# uino-1284p.net
KiCad netlist of a schematic drawn in EAGLE
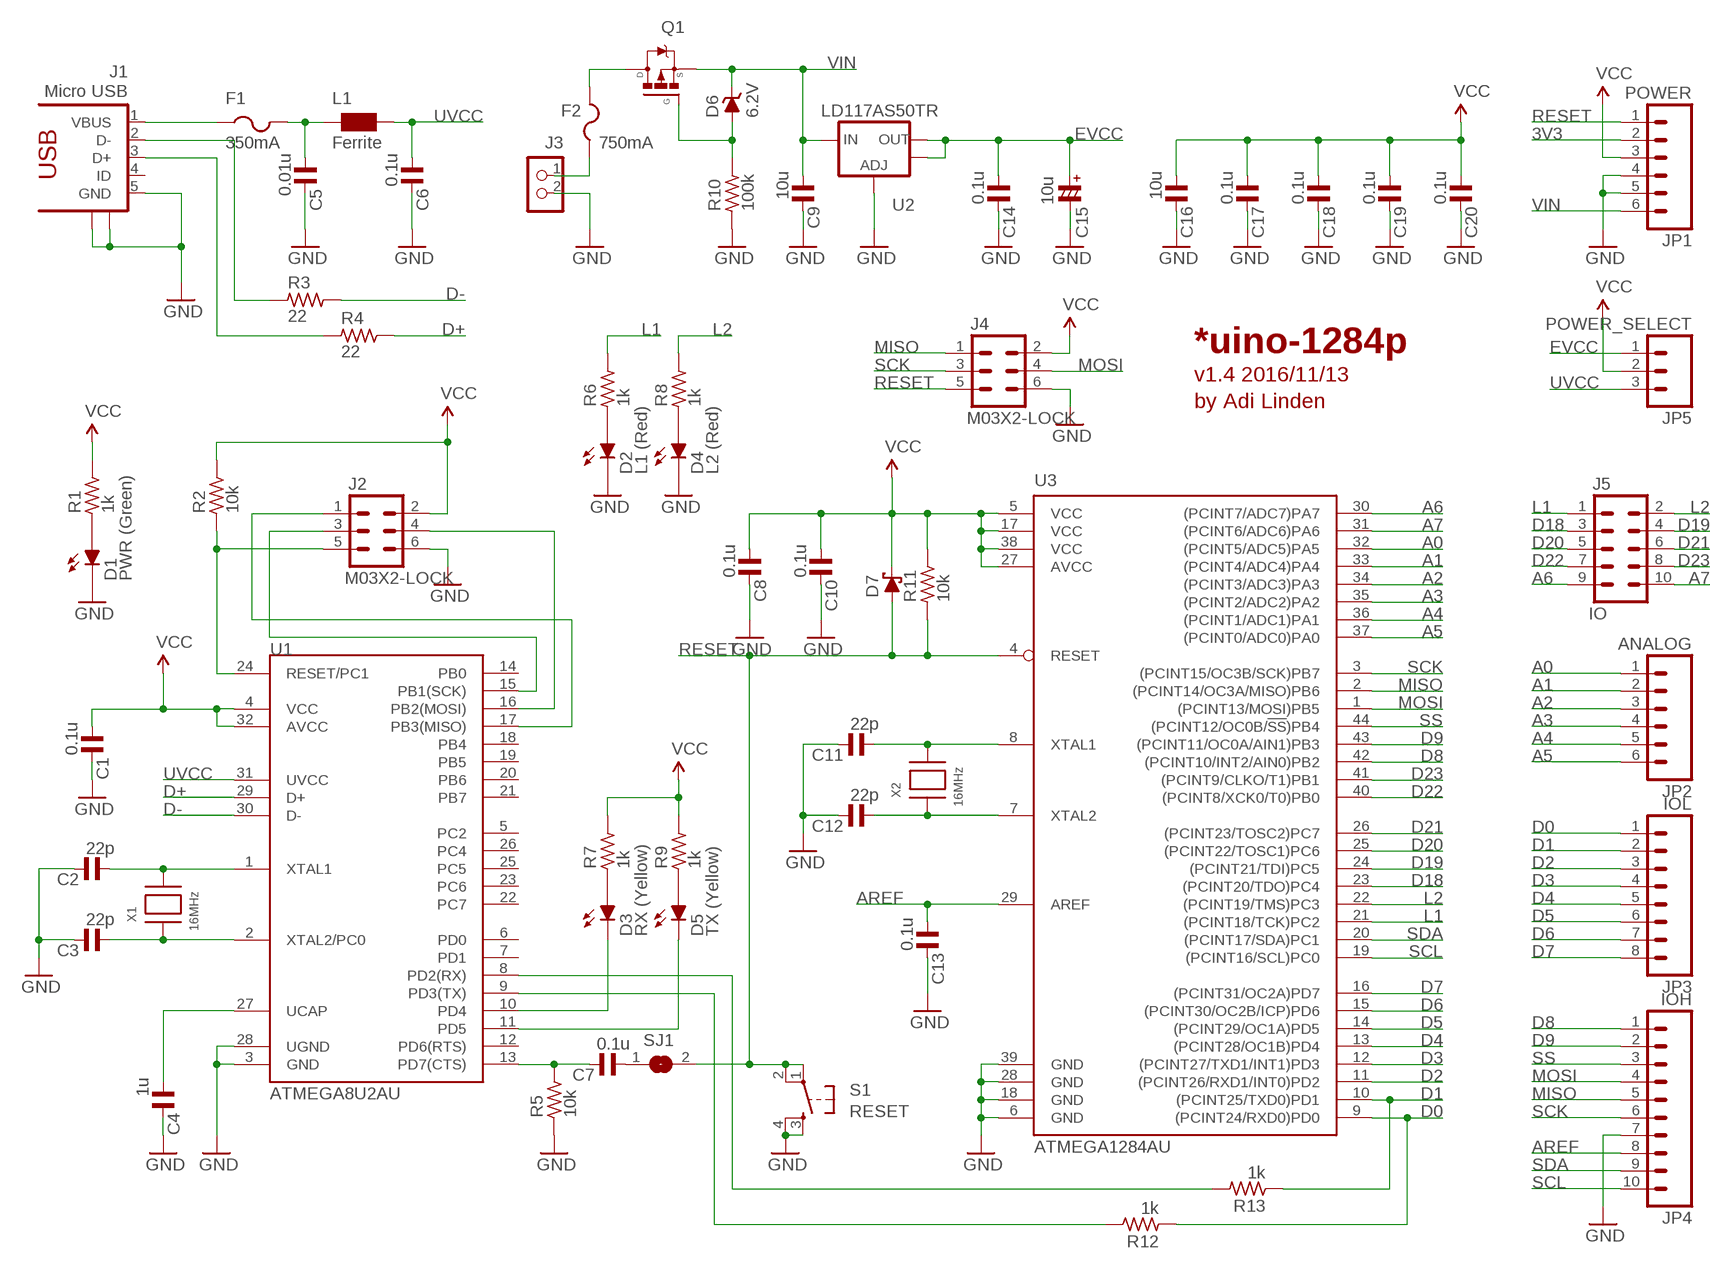
[diagram p0: schematic, sheet 1]

(export (version "E")
  (design (tool "Eeschema 10.0.6"))
  (components
    (comp (ref "C1")
      (value "0.1u")
      (footprint "eagle-import:C0805MP")
      (libsource (lib "eagle-import") (part "C_0805MP"))
    )
    (comp (ref "C2")
      (value "22p")
      (footprint "eagle-import:C0805MP")
      (libsource (lib "eagle-import") (part "C_0805MP"))
    )
    (comp (ref "C3")
      (value "22p")
      (footprint "eagle-import:C0805MP")
      (libsource (lib "eagle-import") (part "C_0805MP"))
    )
    (comp (ref "C4")
      (value "1u")
      (footprint "eagle-import:C0805MP")
      (libsource (lib "eagle-import") (part "C_0805MP"))
    )
    (comp (ref "C5")
      (value "0.01u")
      (footprint "eagle-import:C0805MP")
      (libsource (lib "eagle-import") (part "C_0805MP"))
    )
    (comp (ref "C6")
      (value "0.1u")
      (footprint "eagle-import:C0805MP")
      (libsource (lib "eagle-import") (part "C_0805MP"))
    )
    (comp (ref "C7")
      (value "0.1u")
      (footprint "eagle-import:C0805MP")
      (libsource (lib "eagle-import") (part "C_0805MP"))
    )
    (comp (ref "C8")
      (value "0.1u")
      (footprint "eagle-import:C0805MP")
      (libsource (lib "eagle-import") (part "C_0805MP"))
    )
    (comp (ref "C9")
      (value "10u")
      (footprint "eagle-import:C0805MP")
      (libsource (lib "eagle-import") (part "C_0805MP"))
    )
    (comp (ref "C10")
      (value "0.1u")
      (footprint "eagle-import:C0805MP")
      (libsource (lib "eagle-import") (part "C_0805MP"))
    )
    (comp (ref "C11")
      (value "22p")
      (footprint "eagle-import:C0805MP")
      (libsource (lib "eagle-import") (part "C_0805MP"))
    )
    (comp (ref "C12")
      (value "22p")
      (footprint "eagle-import:C0805MP")
      (libsource (lib "eagle-import") (part "C_0805MP"))
    )
    (comp (ref "C13")
      (value "0.1u")
      (footprint "eagle-import:C0805MP")
      (libsource (lib "eagle-import") (part "C_0805MP"))
    )
    (comp (ref "C14")
      (value "0.1u")
      (footprint "eagle-import:C0805MP")
      (libsource (lib "eagle-import") (part "C_0805MP"))
    )
    (comp (ref "C15")
      (value "10u")
      (footprint "eagle-import:C0805MP_T")
      (libsource (lib "eagle-import") (part "CP_0805MP/T"))
    )
    (comp (ref "C16")
      (value "10u")
      (footprint "eagle-import:C0805MP")
      (libsource (lib "eagle-import") (part "C_0805MP"))
    )
    (comp (ref "C17")
      (value "0.1u")
      (footprint "eagle-import:C0805MP")
      (libsource (lib "eagle-import") (part "C_0805MP"))
    )
    (comp (ref "C18")
      (value "0.1u")
      (footprint "eagle-import:C0805MP")
      (libsource (lib "eagle-import") (part "C_0805MP"))
    )
    (comp (ref "C19")
      (value "0.1u")
      (footprint "eagle-import:C0805MP")
      (libsource (lib "eagle-import") (part "C_0805MP"))
    )
    (comp (ref "C20")
      (value "0.1u")
      (footprint "eagle-import:C0805MP")
      (libsource (lib "eagle-import") (part "C_0805MP"))
    )
    (comp (ref "D1")
      (value "PWR (Green)")
      (footprint "eagle-import:CHIP-LED0805MP")
      (libsource (lib "eagle-import") (part "LEDCHIP-LED0805MP"))
    )
    (comp (ref "D2")
      (value "L1 (Red)")
      (footprint "eagle-import:CHIP-LED0805MP")
      (libsource (lib "eagle-import") (part "LEDCHIP-LED0805MP"))
    )
    (comp (ref "D3")
      (value "RX (Yellow)")
      (footprint "eagle-import:CHIP-LED0805MP")
      (libsource (lib "eagle-import") (part "LEDCHIP-LED0805MP"))
    )
    (comp (ref "D4")
      (value "L2 (Red)")
      (footprint "eagle-import:CHIP-LED0805MP")
      (libsource (lib "eagle-import") (part "LEDCHIP-LED0805MP"))
    )
    (comp (ref "D5")
      (value "TX (Yellow)")
      (footprint "eagle-import:CHIP-LED0805MP")
      (libsource (lib "eagle-import") (part "LEDCHIP-LED0805MP"))
    )
    (comp (ref "D6")
      (value "6.2V")
      (footprint "eagle-import:SOD323")
      (libsource (lib "eagle-import") (part "BZX384"))
    )
    (comp (ref "D7")
      (value "SCHOTTKY-DIODESOD323")
      (footprint "eagle-import:SOD323")
      (libsource (lib "eagle-import") (part "SCHOTTKY-DIODESOD323"))
    )
    (comp (ref "F1")
      (value "350mA")
      (footprint "eagle-import:R0805")
      (libsource (lib "eagle-import") (part "PTCFUSE-0805"))
    )
    (comp (ref "F2")
      (value "750mA")
      (footprint "eagle-import:R0805")
      (libsource (lib "eagle-import") (part "PTCFUSE-0805"))
    )
    (comp (ref "J1")
      (value "Micro USB")
      (footprint "eagle-import:ZX62D-AB-5P8")
      (libsource (lib "eagle-import") (part "USB_MICRO_B_2.0-TH"))
    )
    (comp (ref "J2")
      (value "M03X2-LOCK")
      (footprint "eagle-import:2X03_LOCK")
      (libsource (lib "eagle-import") (part "M03X2-LOCK"))
    )
    (comp (ref "J3")
      (value "CON_TERMINAL_BLOCK_02-5MM")
      (footprint "eagle-import:TERMINAL_BLOCK_2P_5")
      (libsource (lib "eagle-import") (part "CON_TERMINAL_BLOCK_02-5MM"))
    )
    (comp (ref "J4")
      (value "M03X2-LOCK")
      (footprint "eagle-import:2X03_LOCK")
      (libsource (lib "eagle-import") (part "M03X2-LOCK"))
    )
    (comp (ref "J5")
      (value "IO")
      (footprint "eagle-import:2X05")
      (libsource (lib "eagle-import") (part "M05X2"))
    )
    (comp (ref "JP1")
      (value "POWER")
      (footprint "eagle-import:1X06")
      (libsource (lib "eagle-import") (part "M06SIP"))
    )
    (comp (ref "JP2")
      (value "ANALOG")
      (footprint "eagle-import:1X06")
      (libsource (lib "eagle-import") (part "M06SIP"))
    )
    (comp (ref "JP3")
      (value "IOL")
      (footprint "eagle-import:1X08")
      (libsource (lib "eagle-import") (part "M081X08"))
    )
    (comp (ref "JP4")
      (value "IOH")
      (footprint "eagle-import:1X10")
      (libsource (lib "eagle-import") (part "M101X10"))
    )
    (comp (ref "JP5")
      (value "POWER_SELECT")
      (footprint "eagle-import:1X03")
      (libsource (lib "eagle-import") (part "M03PTH"))
    )
    (comp (ref "L1")
      (value "Ferrite")
      (footprint "eagle-import:0805")
      (libsource (lib "eagle-import") (part "WE-CBF_0805"))
    )
    (comp (ref "Q1")
      (value "MMBF0202PLT1")
      (footprint "eagle-import:SOT23")
      (libsource (lib "eagle-import") (part "MMBF0202PLT1"))
    )
    (comp (ref "R1")
      (value "1k")
      (footprint "eagle-import:R0805MP")
      (libsource (lib "eagle-import") (part "R_0805MP"))
    )
    (comp (ref "R2")
      (value "10k")
      (footprint "eagle-import:R0805MP")
      (libsource (lib "eagle-import") (part "R_0805MP"))
    )
    (comp (ref "R3")
      (value "22")
      (footprint "eagle-import:R0805MP")
      (libsource (lib "eagle-import") (part "R_0805MP"))
    )
    (comp (ref "R4")
      (value "22")
      (footprint "eagle-import:R0805MP")
      (libsource (lib "eagle-import") (part "R_0805MP"))
    )
    (comp (ref "R5")
      (value "10k")
      (footprint "eagle-import:R0805MP")
      (libsource (lib "eagle-import") (part "R_0805MP"))
    )
    (comp (ref "R6")
      (value "1k")
      (footprint "eagle-import:R0805MP")
      (libsource (lib "eagle-import") (part "R_0805MP"))
    )
    (comp (ref "R7")
      (value "1k")
      (footprint "eagle-import:R0805MP")
      (libsource (lib "eagle-import") (part "R_0805MP"))
    )
    (comp (ref "R8")
      (value "1k")
      (footprint "eagle-import:R0805MP")
      (libsource (lib "eagle-import") (part "R_0805MP"))
    )
    (comp (ref "R9")
      (value "1k")
      (footprint "eagle-import:R0805MP")
      (libsource (lib "eagle-import") (part "R_0805MP"))
    )
    (comp (ref "R10")
      (value "100k")
      (footprint "eagle-import:R0805MP")
      (libsource (lib "eagle-import") (part "R_0805MP"))
    )
    (comp (ref "R11")
      (value "10k")
      (footprint "eagle-import:R0805MP")
      (libsource (lib "eagle-import") (part "R_0805MP"))
    )
    (comp (ref "R12")
      (value "1k")
      (footprint "eagle-import:R0805MP")
      (libsource (lib "eagle-import") (part "R_0805MP"))
    )
    (comp (ref "R13")
      (value "1k")
      (footprint "eagle-import:R0805MP")
      (libsource (lib "eagle-import") (part "R_0805MP"))
    )
    (comp (ref "S1")
      (value "RESET")
      (footprint "eagle-import:TACTILE_SWITCH_SMD")
      (libsource (lib "eagle-import") (part "TAC_SWITCHSMD"))
    )
    (comp (ref "SJ1") (value "SJ") (footprint "eagle-import:SJ") (libsource (lib "eagle-import") (part "SJ")))
    (comp (ref "U1")
      (value "ATMEGA8U2AU")
      (footprint "eagle-import:TQFP32-08")
      (libsource (lib "eagle-import") (part "ATMEGA8U2AU"))
    )
    (comp (ref "U2")
      (value "LD117AS50TR")
      (footprint "eagle-import:SOT223")
      (libsource (lib "eagle-import") (part "V_REG_LM1117SOT223"))
    )
    (comp (ref "U3")
      (value "ATMEGA1284AU")
      (footprint "eagle-import:TQFP44")
      (fields (field (name "MPN") "ATMEGA644PV-10AU"))
      (libsource (lib "eagle-import") (part "ATMEGA1284P-AU"))
    )
    (comp (ref "X1")
      (value "16MHz")
      (footprint "eagle-import:NX5032")
      (libsource (lib "eagle-import") (part "XTALNX5032"))
    )
    (comp (ref "X2")
      (value "16MHz")
      (footprint "eagle-import:NX5032")
      (libsource (lib "eagle-import") (part "XTALNX5032"))
    )
  )
  (nets
    (net (code "1") (name "/3V3") (class "Default")
      (node (ref "JP1") (pin "2") (pinfunction "2_2") (pintype "passive"))
    )
    (net (code "2") (name "/A0") (class "Default")
      (node (ref "JP2") (pin "1") (pinfunction "1_1") (pintype "passive"))
      (node (ref "U3") (pin "32") (pinfunction "(PCINT5/ADC5)PA5_32") (pintype "bidirectional"))
    )
    (net (code "3") (name "/A1") (class "Default")
      (node (ref "JP2") (pin "2") (pinfunction "2_2") (pintype "passive"))
      (node (ref "U3") (pin "33") (pinfunction "(PCINT4/ADC4)PA4_33") (pintype "bidirectional"))
    )
    (net (code "4") (name "/A2") (class "Default")
      (node (ref "JP2") (pin "3") (pinfunction "3_3") (pintype "passive"))
      (node (ref "U3") (pin "34") (pinfunction "(PCINT3/ADC3)PA3_34") (pintype "bidirectional"))
    )
    (net (code "5") (name "/A3") (class "Default")
      (node (ref "JP2") (pin "4") (pinfunction "4_4") (pintype "passive"))
      (node (ref "U3") (pin "35") (pinfunction "(PCINT2/ADC2)PA2_35") (pintype "bidirectional"))
    )
    (net (code "6") (name "/A4") (class "Default")
      (node (ref "JP2") (pin "5") (pinfunction "5_5") (pintype "passive"))
      (node (ref "U3") (pin "36") (pinfunction "(PCINT1/ADC1)PA1_36") (pintype "bidirectional"))
    )
    (net (code "7") (name "/A5") (class "Default")
      (node (ref "JP2") (pin "6") (pinfunction "6_6") (pintype "passive"))
      (node (ref "U3") (pin "37") (pinfunction "(PCINT0/ADC0)PA0_37") (pintype "bidirectional"))
    )
    (net (code "8") (name "/A6") (class "Default")
      (node (ref "J5") (pin "9") (pinfunction "9_9") (pintype "passive"))
      (node (ref "U3") (pin "30") (pinfunction "(PCINT7/ADC7)PA7_30") (pintype "bidirectional"))
    )
    (net (code "9") (name "/A7") (class "Default")
      (node (ref "J5") (pin "10") (pinfunction "10_10") (pintype "passive"))
      (node (ref "U3") (pin "31") (pinfunction "(PCINT6/ADC6)PA6_31") (pintype "bidirectional"))
    )
    (net (code "10") (name "/AREF") (class "Default")
      (node (ref "C13") (pin "1") (pinfunction "1_1") (pintype "passive"))
      (node (ref "JP4") (pin "8") (pinfunction "8_8") (pintype "passive"))
      (node (ref "U3") (pin "29") (pinfunction "AREF_29") (pintype "passive"))
    )
    (net (code "11") (name "/D+") (class "Default")
      (node (ref "R4") (pin "2") (pinfunction "2_2") (pintype "passive"))
      (node (ref "U1") (pin "29") (pinfunction "D+_29") (pintype "bidirectional"))
    )
    (net (code "12") (name "/D-") (class "Default")
      (node (ref "R3") (pin "2") (pinfunction "2_2") (pintype "passive"))
      (node (ref "U1") (pin "30") (pinfunction "D-_30") (pintype "bidirectional"))
    )
    (net (code "13") (name "/D0") (class "Default")
      (node (ref "JP3") (pin "1") (pinfunction "1_1") (pintype "passive"))
      (node (ref "R12") (pin "1") (pinfunction "1_1") (pintype "passive"))
      (node (ref "U3") (pin "9") (pinfunction "(PCINT24/RXD0)PD0_9") (pintype "bidirectional"))
    )
    (net (code "14") (name "/D1") (class "Default")
      (node (ref "JP3") (pin "2") (pinfunction "2_2") (pintype "passive"))
      (node (ref "R13") (pin "1") (pinfunction "1_1") (pintype "passive"))
      (node (ref "U3") (pin "10") (pinfunction "(PCINT25/TXD0)PD1_10") (pintype "bidirectional"))
    )
    (net (code "15") (name "/D2") (class "Default")
      (node (ref "JP3") (pin "3") (pinfunction "3_3") (pintype "passive"))
      (node (ref "U3") (pin "11") (pinfunction "(PCINT26/RXD1/INT0)PD2_11") (pintype "bidirectional"))
    )
    (net (code "16") (name "/D3") (class "Default")
      (node (ref "JP3") (pin "4") (pinfunction "4_4") (pintype "passive"))
      (node (ref "U3") (pin "12") (pinfunction "(PCINT27/TXD1/INT1)PD3_12") (pintype "bidirectional"))
    )
    (net (code "17") (name "/D4") (class "Default")
      (node (ref "JP3") (pin "5") (pinfunction "5_5") (pintype "passive"))
      (node (ref "U3") (pin "13") (pinfunction "(PCINT28/OC1B)PD4_13") (pintype "bidirectional"))
    )
    (net (code "18") (name "/D5") (class "Default")
      (node (ref "JP3") (pin "6") (pinfunction "6_6") (pintype "passive"))
      (node (ref "U3") (pin "14") (pinfunction "(PCINT29/OC1A)PD5_14") (pintype "bidirectional"))
    )
    (net (code "19") (name "/D6") (class "Default")
      (node (ref "JP3") (pin "7") (pinfunction "7_7") (pintype "passive"))
      (node (ref "U3") (pin "15") (pinfunction "(PCINT30/OC2B/ICP)PD6_15") (pintype "bidirectional"))
    )
    (net (code "20") (name "/D7") (class "Default")
      (node (ref "JP3") (pin "8") (pinfunction "8_8") (pintype "passive"))
      (node (ref "U3") (pin "16") (pinfunction "(PCINT31/OC2A)PD7_16") (pintype "bidirectional"))
    )
    (net (code "21") (name "/D8") (class "Default")
      (node (ref "JP4") (pin "1") (pinfunction "1_1") (pintype "passive"))
      (node (ref "U3") (pin "42") (pinfunction "(PCINT10/INT2/AIN0)PB2_42") (pintype "bidirectional"))
    )
    (net (code "22") (name "/D9") (class "Default")
      (node (ref "JP4") (pin "2") (pinfunction "2_2") (pintype "passive"))
      (node (ref "U3") (pin "43") (pinfunction "(PCINT11/OC0A/AIN1)PB3_43") (pintype "bidirectional"))
    )
    (net (code "23") (name "/D18") (class "Default")
      (node (ref "J5") (pin "3") (pinfunction "3_3") (pintype "passive"))
      (node (ref "U3") (pin "23") (pinfunction "(PCINT20/TDO)PC4_23") (pintype "output"))
    )
    (net (code "24") (name "/D19") (class "Default")
      (node (ref "J5") (pin "4") (pinfunction "4_4") (pintype "passive"))
      (node (ref "U3") (pin "24") (pinfunction "(PCINT21/TDI)PC5_24") (pintype "output"))
    )
    (net (code "25") (name "/D20") (class "Default")
      (node (ref "J5") (pin "5") (pinfunction "5_5") (pintype "passive"))
      (node (ref "U3") (pin "25") (pinfunction "(PCINT22/TOSC1)PC6_25") (pintype "output"))
    )
    (net (code "26") (name "/D21") (class "Default")
      (node (ref "J5") (pin "6") (pinfunction "6_6") (pintype "passive"))
      (node (ref "U3") (pin "26") (pinfunction "(PCINT23/TOSC2)PC7_26") (pintype "output"))
    )
    (net (code "27") (name "/D22") (class "Default")
      (node (ref "J5") (pin "7") (pinfunction "7_7") (pintype "passive"))
      (node (ref "U3") (pin "40") (pinfunction "(PCINT8/XCK0/T0)PB0_40") (pintype "bidirectional"))
    )
    (net (code "28") (name "/D23") (class "Default")
      (node (ref "J5") (pin "8") (pinfunction "8_8") (pintype "passive"))
      (node (ref "U3") (pin "41") (pinfunction "(PCINT9/CLKO/T1)PB1_41") (pintype "bidirectional"))
    )
    (net (code "29") (name "/EVCC") (class "Default")
      (node (ref "C14") (pin "1") (pinfunction "1_1") (pintype "passive"))
      (node (ref "C15") (pin "+") (pinfunction "+_+") (pintype "passive"))
      (node (ref "JP5") (pin "1") (pinfunction "1_1") (pintype "passive"))
      (node (ref "U2") (pin "2") (pinfunction "OUT_2") (pintype "power_in"))
      (node (ref "U2") (pin "4") (pinfunction "OUT_4") (pintype "power_in"))
    )
    (net (code "30") (name "/L1") (class "Default")
      (node (ref "J5") (pin "1") (pinfunction "1_1") (pintype "passive"))
      (node (ref "R6") (pin "2") (pinfunction "2_2") (pintype "passive"))
      (node (ref "U3") (pin "21") (pinfunction "(PCINT18/TCK)PC2_21") (pintype "output"))
    )
    (net (code "31") (name "/L2") (class "Default")
      (node (ref "J5") (pin "2") (pinfunction "2_2") (pintype "passive"))
      (node (ref "R8") (pin "2") (pinfunction "2_2") (pintype "passive"))
      (node (ref "U3") (pin "22") (pinfunction "(PCINT19/TMS)PC3_22") (pintype "output"))
    )
    (net (code "32") (name "/MISO") (class "Default")
      (node (ref "J4") (pin "1") (pinfunction "1_1") (pintype "passive"))
      (node (ref "JP4") (pin "5") (pinfunction "5_5") (pintype "passive"))
      (node (ref "U3") (pin "2") (pinfunction "(PCINT14/OC3A/MISO)PB6_2") (pintype "bidirectional"))
    )
    (net (code "33") (name "/MOSI") (class "Default")
      (node (ref "J4") (pin "4") (pinfunction "4_4") (pintype "passive"))
      (node (ref "JP4") (pin "4") (pinfunction "4_4") (pintype "passive"))
      (node (ref "U3") (pin "1") (pinfunction "(PCINT13/MOSI)PB5_1") (pintype "bidirectional"))
    )
    (net (code "34") (name "/RESET") (class "Default")
      (node (ref "D7") (pin "A") (pinfunction "A_A") (pintype "passive"))
      (node (ref "J4") (pin "5") (pinfunction "5_5") (pintype "passive"))
      (node (ref "JP1") (pin "1") (pinfunction "1_1") (pintype "passive"))
      (node (ref "R11") (pin "1") (pinfunction "1_1") (pintype "passive"))
      (node (ref "S1") (pin "1") (pinfunction "1_1") (pintype "passive"))
      (node (ref "S1") (pin "2") (pinfunction "2_2") (pintype "passive"))
      (node (ref "SJ1") (pin "2") (pinfunction "2_2") (pintype "passive"))
      (node (ref "U3") (pin "4") (pinfunction "RESET_4") (pintype "input"))
    )
    (net (code "35") (name "/SCK") (class "Default")
      (node (ref "J4") (pin "3") (pinfunction "3_3") (pintype "passive"))
      (node (ref "JP4") (pin "6") (pinfunction "6_6") (pintype "passive"))
      (node (ref "U3") (pin "3") (pinfunction "(PCINT15/OC3B/SCK)PB7_3") (pintype "bidirectional"))
    )
    (net (code "36") (name "/SCL") (class "Default")
      (node (ref "JP4") (pin "10") (pinfunction "10_10") (pintype "passive"))
      (node (ref "U3") (pin "19") (pinfunction "(PCINT16/SCL)PC0_19") (pintype "output"))
    )
    (net (code "37") (name "/SDA") (class "Default")
      (node (ref "JP4") (pin "9") (pinfunction "9_9") (pintype "passive"))
      (node (ref "U3") (pin "20") (pinfunction "(PCINT17/SDA)PC1_20") (pintype "output"))
    )
    (net (code "38") (name "/SS") (class "Default")
      (node (ref "JP4") (pin "3") (pinfunction "3_3") (pintype "passive"))
      (node (ref "U3") (pin "44") (pinfunction "(PCINT12/OC0B/~{SS})PB4_44") (pintype "bidirectional"))
    )
    (net (code "39") (name "/UVCC") (class "Default")
      (node (ref "C6") (pin "1") (pinfunction "1_1") (pintype "passive"))
      (node (ref "JP5") (pin "3") (pinfunction "3_3") (pintype "passive"))
      (node (ref "L1") (pin "2") (pinfunction "2_2") (pintype "passive"))
      (node (ref "U1") (pin "31") (pinfunction "UVCC_31") (pintype "bidirectional"))
    )
    (net (code "40") (name "/VIN") (class "Default")
      (node (ref "C9") (pin "1") (pinfunction "1_1") (pintype "passive"))
      (node (ref "D6") (pin "C") (pinfunction "C_C") (pintype "passive"))
      (node (ref "JP1") (pin "6") (pinfunction "6_6") (pintype "passive"))
      (node (ref "Q1") (pin "2") (pinfunction "S_2") (pintype "passive"))
      (node (ref "U2") (pin "3") (pinfunction "IN_3") (pintype "input"))
    )
    (net (code "41") (name "GND") (class "Default")
      (node (ref "C1") (pin "2") (pinfunction "2_2") (pintype "passive"))
      (node (ref "C10") (pin "2") (pinfunction "2_2") (pintype "passive"))
      (node (ref "C11") (pin "2") (pinfunction "2_2") (pintype "passive"))
      (node (ref "C12") (pin "2") (pinfunction "2_2") (pintype "passive"))
      (node (ref "C13") (pin "2") (pinfunction "2_2") (pintype "passive"))
      (node (ref "C14") (pin "2") (pinfunction "2_2") (pintype "passive"))
      (node (ref "C15") (pin "-") (pinfunction "-_-") (pintype "passive"))
      (node (ref "C16") (pin "2") (pinfunction "2_2") (pintype "passive"))
      (node (ref "C17") (pin "2") (pinfunction "2_2") (pintype "passive"))
      (node (ref "C18") (pin "2") (pinfunction "2_2") (pintype "passive"))
      (node (ref "C19") (pin "2") (pinfunction "2_2") (pintype "passive"))
      (node (ref "C2") (pin "2") (pinfunction "2_2") (pintype "passive"))
      (node (ref "C20") (pin "2") (pinfunction "2_2") (pintype "passive"))
      (node (ref "C3") (pin "2") (pinfunction "2_2") (pintype "passive"))
      (node (ref "C4") (pin "2") (pinfunction "2_2") (pintype "passive"))
      (node (ref "C5") (pin "2") (pinfunction "2_2") (pintype "passive"))
      (node (ref "C6") (pin "2") (pinfunction "2_2") (pintype "passive"))
      (node (ref "C8") (pin "2") (pinfunction "2_2") (pintype "passive"))
      (node (ref "C9") (pin "2") (pinfunction "2_2") (pintype "passive"))
      (node (ref "D1") (pin "C") (pinfunction "C_C") (pintype "passive"))
      (node (ref "D2") (pin "C") (pinfunction "C_C") (pintype "passive"))
      (node (ref "D4") (pin "C") (pinfunction "C_C") (pintype "passive"))
      (node (ref "J1") (pin "5") (pinfunction "GND_5") (pintype "passive"))
      (node (ref "J1") (pin "S1") (pinfunction "S1_S1") (pintype "passive"))
      (node (ref "J1") (pin "S2") (pinfunction "S2_S2") (pintype "passive"))
      (node (ref "J2") (pin "6") (pinfunction "6_6") (pintype "passive"))
      (node (ref "J3") (pin "2") (pinfunction "2_2") (pintype "passive"))
      (node (ref "J4") (pin "6") (pinfunction "6_6") (pintype "passive"))
      (node (ref "JP1") (pin "4") (pinfunction "4_4") (pintype "passive"))
      (node (ref "JP1") (pin "5") (pinfunction "5_5") (pintype "passive"))
      (node (ref "JP4") (pin "7") (pinfunction "7_7") (pintype "passive"))
      (node (ref "R10") (pin "1") (pinfunction "1_1") (pintype "passive"))
      (node (ref "R5") (pin "1") (pinfunction "1_1") (pintype "passive"))
      (node (ref "S1") (pin "3") (pinfunction "3_3") (pintype "passive"))
      (node (ref "S1") (pin "4") (pinfunction "4_4") (pintype "passive"))
      (node (ref "U1") (pin "28") (pinfunction "UGND_28") (pintype "bidirectional"))
      (node (ref "U1") (pin "3") (pinfunction "GND_3") (pintype "bidirectional"))
      (node (ref "U2") (pin "1") (pinfunction "ADJ_1") (pintype "input"))
      (node (ref "U3") (pin "18") (pinfunction "GND_18") (pintype "power_in"))
      (node (ref "U3") (pin "28") (pinfunction "GND_28") (pintype "power_in"))
      (node (ref "U3") (pin "39") (pinfunction "GND_39") (pintype "power_in"))
      (node (ref "U3") (pin "6") (pinfunction "GND_6") (pintype "power_in"))
    )
    (net (code "42") (name "Net-(C5-Pad1)") (class "Default")
      (node (ref "C5") (pin "1") (pinfunction "1_1") (pintype "passive"))
      (node (ref "F1") (pin "2") (pinfunction "2_2") (pintype "passive"))
      (node (ref "L1") (pin "1") (pinfunction "1_1") (pintype "passive"))
    )
    (net (code "43") (name "Net-(C7-Pad1)") (class "Default")
      (node (ref "C7") (pin "1") (pinfunction "1_1") (pintype "passive"))
      (node (ref "SJ1") (pin "1") (pinfunction "1_1") (pintype "passive"))
    )
    (net (code "44") (name "Net-(D1-PadA)") (class "Default")
      (node (ref "D1") (pin "A") (pinfunction "A_A") (pintype "passive"))
      (node (ref "R1") (pin "1") (pinfunction "1_1") (pintype "passive"))
    )
    (net (code "45") (name "Net-(D2-PadA)") (class "Default")
      (node (ref "D2") (pin "A") (pinfunction "A_A") (pintype "passive"))
      (node (ref "R6") (pin "1") (pinfunction "1_1") (pintype "passive"))
    )
    (net (code "46") (name "Net-(D3-PadA)") (class "Default")
      (node (ref "D3") (pin "A") (pinfunction "A_A") (pintype "passive"))
      (node (ref "R7") (pin "1") (pinfunction "1_1") (pintype "passive"))
    )
    (net (code "47") (name "Net-(D4-PadA)") (class "Default")
      (node (ref "D4") (pin "A") (pinfunction "A_A") (pintype "passive"))
      (node (ref "R8") (pin "1") (pinfunction "1_1") (pintype "passive"))
    )
    (net (code "48") (name "Net-(D5-PadA)") (class "Default")
      (node (ref "D5") (pin "A") (pinfunction "A_A") (pintype "passive"))
      (node (ref "R9") (pin "1") (pinfunction "1_1") (pintype "passive"))
    )
    (net (code "49") (name "Net-(F2-Pad1)") (class "Default")
      (node (ref "F2") (pin "1") (pinfunction "1_1") (pintype "passive"))
      (node (ref "J3") (pin "1") (pinfunction "1_1") (pintype "passive"))
    )
    (net (code "50") (name "Net-(J1-D+)") (class "Default")
      (node (ref "J1") (pin "3") (pinfunction "D+_3") (pintype "passive"))
      (node (ref "R4") (pin "1") (pinfunction "1_1") (pintype "passive"))
    )
    (net (code "51") (name "Net-(J1-D-)") (class "Default")
      (node (ref "J1") (pin "2") (pinfunction "D-_2") (pintype "passive"))
      (node (ref "R3") (pin "1") (pinfunction "1_1") (pintype "passive"))
    )
    (net (code "52") (name "Net-(J1-VBUS)") (class "Default")
      (node (ref "F1") (pin "1") (pinfunction "1_1") (pintype "passive"))
      (node (ref "J1") (pin "1") (pinfunction "VBUS_1") (pintype "passive"))
    )
    (net (code "53") (name "Net-(Q1-D)") (class "Default")
      (node (ref "F2") (pin "2") (pinfunction "2_2") (pintype "passive"))
      (node (ref "Q1") (pin "3") (pinfunction "D_3") (pintype "passive"))
    )
    (net (code "54") (name "Net-(Q1-G)") (class "Default")
      (node (ref "D6") (pin "A") (pinfunction "A_A") (pintype "passive"))
      (node (ref "Q1") (pin "1") (pinfunction "G_1") (pintype "passive"))
      (node (ref "R10") (pin "2") (pinfunction "2_2") (pintype "passive"))
    )
    (net (code "55") (name "Net-(U1-PB1(SCK))") (class "Default")
      (node (ref "J2") (pin "3") (pinfunction "3_3") (pintype "passive"))
      (node (ref "U1") (pin "15") (pinfunction "PB1(SCK)_15") (pintype "bidirectional"))
    )
    (net (code "56") (name "Net-(U1-PB2(MOSI))") (class "Default")
      (node (ref "J2") (pin "4") (pinfunction "4_4") (pintype "passive"))
      (node (ref "U1") (pin "16") (pinfunction "PB2(MOSI)_16") (pintype "bidirectional"))
    )
    (net (code "57") (name "Net-(U1-PB3(MISO))") (class "Default")
      (node (ref "J2") (pin "1") (pinfunction "1_1") (pintype "passive"))
      (node (ref "U1") (pin "17") (pinfunction "PB3(MISO)_17") (pintype "bidirectional"))
    )
    (net (code "58") (name "Net-(U1-PD2(RX))") (class "Default")
      (node (ref "R13") (pin "2") (pinfunction "2_2") (pintype "passive"))
      (node (ref "U1") (pin "8") (pinfunction "PD2(RX)_8") (pintype "bidirectional"))
    )
    (net (code "59") (name "Net-(U1-PD3(TX))") (class "Default")
      (node (ref "R12") (pin "2") (pinfunction "2_2") (pintype "passive"))
      (node (ref "U1") (pin "9") (pinfunction "PD3(TX)_9") (pintype "bidirectional"))
    )
    (net (code "60") (name "Net-(U1-PD4)") (class "Default")
      (node (ref "D3") (pin "C") (pinfunction "C_C") (pintype "passive"))
      (node (ref "U1") (pin "10") (pinfunction "PD4_10") (pintype "bidirectional"))
    )
    (net (code "61") (name "Net-(U1-PD5)") (class "Default")
      (node (ref "D5") (pin "C") (pinfunction "C_C") (pintype "passive"))
      (node (ref "U1") (pin "11") (pinfunction "PD5_11") (pintype "bidirectional"))
    )
    (net (code "62") (name "Net-(U1-PD7(CTS))") (class "Default")
      (node (ref "C7") (pin "2") (pinfunction "2_2") (pintype "passive"))
      (node (ref "R5") (pin "2") (pinfunction "2_2") (pintype "passive"))
      (node (ref "U1") (pin "13") (pinfunction "PD7(CTS)_13") (pintype "bidirectional"))
    )
    (net (code "63") (name "Net-(U1-RESET{slash}PC1)") (class "Default")
      (node (ref "J2") (pin "5") (pinfunction "5_5") (pintype "passive"))
      (node (ref "R2") (pin "1") (pinfunction "1_1") (pintype "passive"))
      (node (ref "U1") (pin "24") (pinfunction "RESET/PC1_24") (pintype "bidirectional"))
    )
    (net (code "64") (name "Net-(U1-UCAP)") (class "Default")
      (node (ref "C4") (pin "1") (pinfunction "1_1") (pintype "passive"))
      (node (ref "U1") (pin "27") (pinfunction "UCAP_27") (pintype "bidirectional"))
    )
    (net (code "65") (name "Net-(U1-XTAL1)") (class "Default")
      (node (ref "C2") (pin "1") (pinfunction "1_1") (pintype "passive"))
      (node (ref "U1") (pin "1") (pinfunction "XTAL1_1") (pintype "bidirectional"))
      (node (ref "X1") (pin "P$2") (pinfunction "P$2_P$2") (pintype "bidirectional"))
    )
    (net (code "66") (name "Net-(U1-XTAL2{slash}PC0)") (class "Default")
      (node (ref "C3") (pin "1") (pinfunction "1_1") (pintype "passive"))
      (node (ref "U1") (pin "2") (pinfunction "XTAL2/PC0_2") (pintype "bidirectional"))
      (node (ref "X1") (pin "P$1") (pinfunction "P$1_P$1") (pintype "bidirectional"))
    )
    (net (code "67") (name "Net-(U3-XTAL1)") (class "Default")
      (node (ref "C11") (pin "1") (pinfunction "1_1") (pintype "passive"))
      (node (ref "U3") (pin "8") (pinfunction "XTAL1_8") (pintype "bidirectional"))
      (node (ref "X2") (pin "P$2") (pinfunction "P$2_P$2") (pintype "bidirectional"))
    )
    (net (code "68") (name "Net-(U3-XTAL2)") (class "Default")
      (node (ref "C12") (pin "1") (pinfunction "1_1") (pintype "passive"))
      (node (ref "U3") (pin "7") (pinfunction "XTAL2_7") (pintype "bidirectional"))
      (node (ref "X2") (pin "P$1") (pinfunction "P$1_P$1") (pintype "bidirectional"))
    )
    (net (code "69") (name "VCC") (class "Default")
      (node (ref "C1") (pin "1") (pinfunction "1_1") (pintype "passive"))
      (node (ref "C10") (pin "1") (pinfunction "1_1") (pintype "passive"))
      (node (ref "C16") (pin "1") (pinfunction "1_1") (pintype "passive"))
      (node (ref "C17") (pin "1") (pinfunction "1_1") (pintype "passive"))
      (node (ref "C18") (pin "1") (pinfunction "1_1") (pintype "passive"))
      (node (ref "C19") (pin "1") (pinfunction "1_1") (pintype "passive"))
      (node (ref "C20") (pin "1") (pinfunction "1_1") (pintype "passive"))
      (node (ref "C8") (pin "1") (pinfunction "1_1") (pintype "passive"))
      (node (ref "D7") (pin "C") (pinfunction "C_C") (pintype "passive"))
      (node (ref "J2") (pin "2") (pinfunction "2_2") (pintype "passive"))
      (node (ref "J4") (pin "2") (pinfunction "2_2") (pintype "passive"))
      (node (ref "JP1") (pin "3") (pinfunction "3_3") (pintype "passive"))
      (node (ref "JP5") (pin "2") (pinfunction "2_2") (pintype "passive"))
      (node (ref "R1") (pin "2") (pinfunction "2_2") (pintype "passive"))
      (node (ref "R11") (pin "2") (pinfunction "2_2") (pintype "passive"))
      (node (ref "R2") (pin "2") (pinfunction "2_2") (pintype "passive"))
      (node (ref "R7") (pin "2") (pinfunction "2_2") (pintype "passive"))
      (node (ref "R9") (pin "2") (pinfunction "2_2") (pintype "passive"))
      (node (ref "U1") (pin "32") (pinfunction "AVCC_32") (pintype "bidirectional"))
      (node (ref "U1") (pin "4") (pinfunction "VCC_4") (pintype "bidirectional"))
      (node (ref "U3") (pin "17") (pinfunction "VCC_17") (pintype "power_in"))
      (node (ref "U3") (pin "27") (pinfunction "AVCC_27") (pintype "power_in"))
      (node (ref "U3") (pin "38") (pinfunction "VCC_38") (pintype "power_in"))
      (node (ref "U3") (pin "5") (pinfunction "VCC_5") (pintype "power_in"))
    )
    (net (code "70") (name "unconnected-(J1-ID-Pad4)") (class "Default")
      (node (ref "J1") (pin "4") (pinfunction "ID_4") (pintype "passive"))
    )
    (net (code "71") (name "unconnected-(U1-PB0-Pad14)") (class "Default")
      (node (ref "U1") (pin "14") (pinfunction "PB0_14") (pintype "bidirectional"))
    )
    (net (code "72") (name "unconnected-(U1-PB4-Pad18)") (class "Default")
      (node (ref "U1") (pin "18") (pinfunction "PB4_18") (pintype "bidirectional"))
    )
    (net (code "73") (name "unconnected-(U1-PB5-Pad19)") (class "Default")
      (node (ref "U1") (pin "19") (pinfunction "PB5_19") (pintype "bidirectional"))
    )
    (net (code "74") (name "unconnected-(U1-PB6-Pad20)") (class "Default")
      (node (ref "U1") (pin "20") (pinfunction "PB6_20") (pintype "bidirectional"))
    )
    (net (code "75") (name "unconnected-(U1-PB7-Pad21)") (class "Default")
      (node (ref "U1") (pin "21") (pinfunction "PB7_21") (pintype "bidirectional"))
    )
    (net (code "76") (name "unconnected-(U1-PC2-Pad5)") (class "Default")
      (node (ref "U1") (pin "5") (pinfunction "PC2_5") (pintype "bidirectional"))
    )
    (net (code "77") (name "unconnected-(U1-PC4-Pad26)") (class "Default")
      (node (ref "U1") (pin "26") (pinfunction "PC4_26") (pintype "bidirectional"))
    )
    (net (code "78") (name "unconnected-(U1-PC5-Pad25)") (class "Default")
      (node (ref "U1") (pin "25") (pinfunction "PC5_25") (pintype "bidirectional"))
    )
    (net (code "79") (name "unconnected-(U1-PC6-Pad23)") (class "Default")
      (node (ref "U1") (pin "23") (pinfunction "PC6_23") (pintype "bidirectional"))
    )
    (net (code "80") (name "unconnected-(U1-PC7-Pad22)") (class "Default")
      (node (ref "U1") (pin "22") (pinfunction "PC7_22") (pintype "bidirectional"))
    )
    (net (code "81") (name "unconnected-(U1-PD0-Pad6)") (class "Default")
      (node (ref "U1") (pin "6") (pinfunction "PD0_6") (pintype "bidirectional"))
    )
    (net (code "82") (name "unconnected-(U1-PD1-Pad7)") (class "Default")
      (node (ref "U1") (pin "7") (pinfunction "PD1_7") (pintype "bidirectional"))
    )
    (net (code "83") (name "unconnected-(U1-PD6(RTS)-Pad12)") (class "Default")
      (node (ref "U1") (pin "12") (pinfunction "PD6(RTS)_12") (pintype "bidirectional"))
    )
  )
)
